# Power_supply.net
KiCad netlist of a schematic drawn in Altium Designer
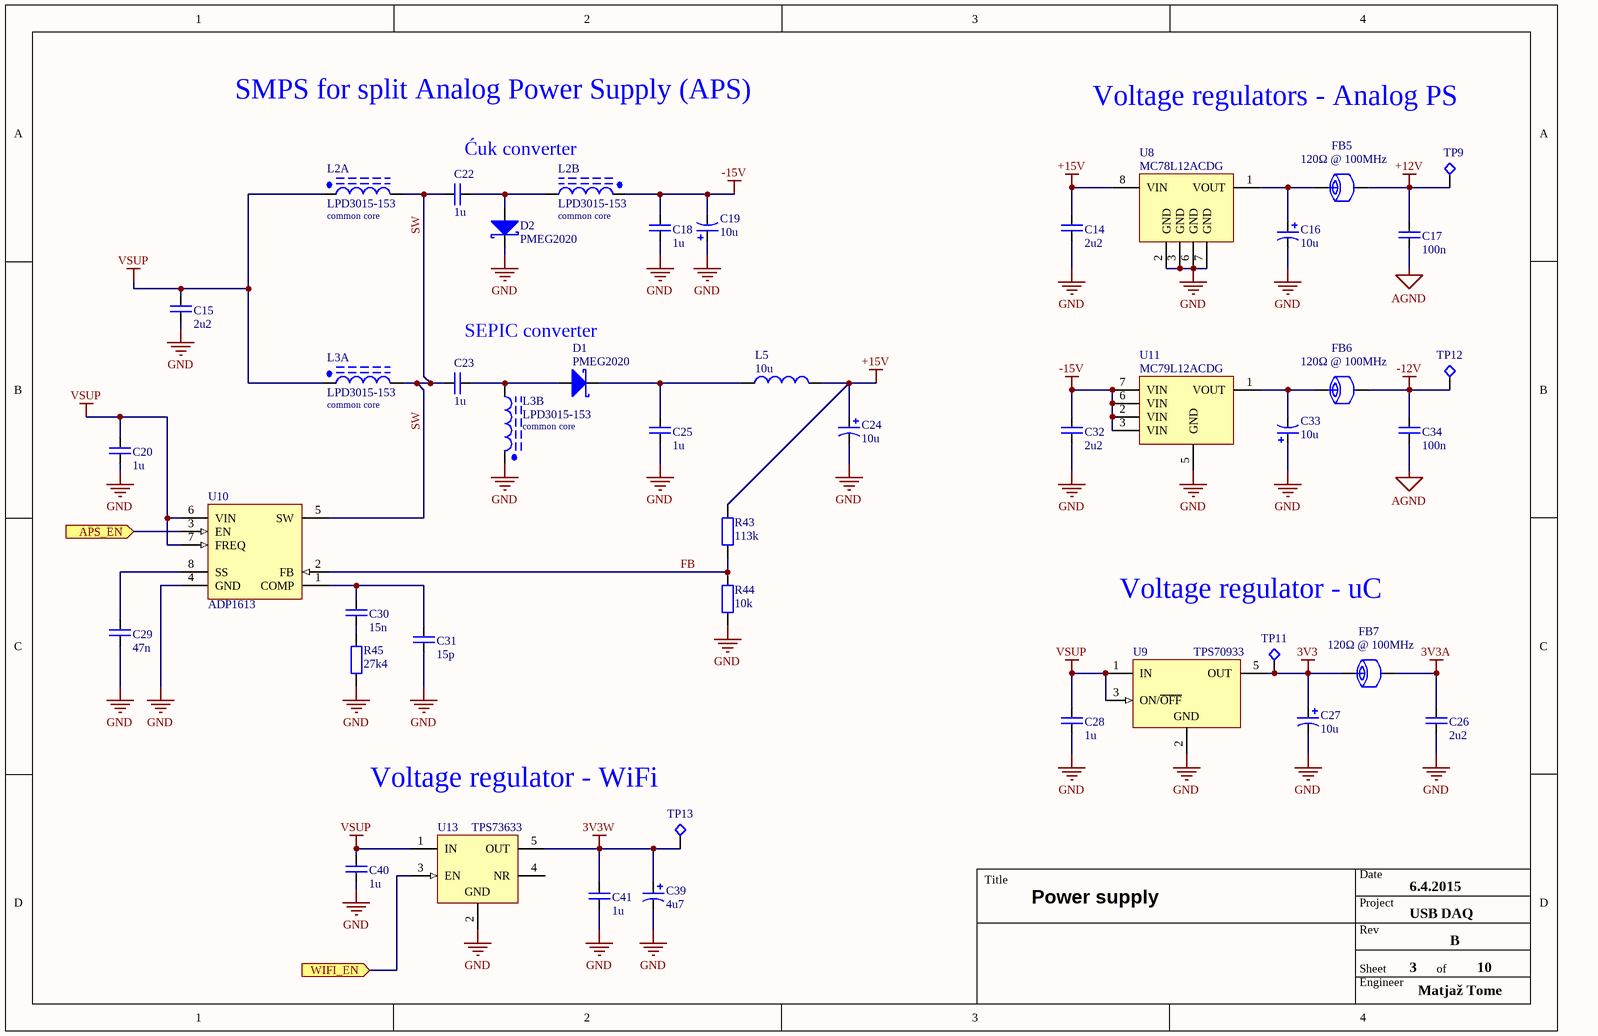
[diagram p0: Power_supply.SchDoc]

(export (version "E")
  (design (tool "Eeschema 10.0.6"))
  (components
    (comp (ref "C14")
      (value "2u2")
      (footprint "C_0603")
      (description "Generic capacitor")
      (libsource (lib "DAQ_REV_B") (part "Capacitor"))
    )
    (comp (ref "C15")
      (value "2u2")
      (footprint "C_0603")
      (description "Generic capacitor")
      (libsource (lib "DAQ_REV_B") (part "Capacitor"))
    )
    (comp (ref "C16")
      (value "10u")
      (footprint "Tantalum Case A")
      (description "Generic polarized capacitor")
      (libsource (lib "DAQ_REV_B") (part "Capacitor - polarized"))
    )
    (comp (ref "C17")
      (value "100n")
      (footprint "C_0603")
      (description "Generic capacitor")
      (libsource (lib "DAQ_REV_B") (part "Capacitor"))
    )
    (comp (ref "C18")
      (value "1u")
      (footprint "C_0603")
      (description "Generic capacitor")
      (libsource (lib "DAQ_REV_B") (part "Capacitor"))
    )
    (comp (ref "C19")
      (value "10u")
      (footprint "Tantalum Case A")
      (description "Generic polarized capacitor")
      (libsource (lib "DAQ_REV_B") (part "Capacitor - polarized"))
    )
    (comp (ref "C20")
      (value "1u")
      (footprint "C_0603")
      (description "Generic capacitor")
      (libsource (lib "DAQ_REV_B") (part "Capacitor"))
    )
    (comp (ref "C22")
      (value "1u")
      (footprint "C_0603")
      (description "Generic capacitor")
      (libsource (lib "DAQ_REV_B") (part "Capacitor"))
    )
    (comp (ref "C23")
      (value "1u")
      (footprint "C_0603")
      (description "Generic capacitor")
      (libsource (lib "DAQ_REV_B") (part "Capacitor"))
    )
    (comp (ref "C24")
      (value "10u")
      (footprint "Tantalum Case A")
      (description "Generic polarized capacitor")
      (libsource (lib "DAQ_REV_B") (part "Capacitor - polarized"))
    )
    (comp (ref "C25")
      (value "1u")
      (footprint "C_0603")
      (description "Generic capacitor")
      (libsource (lib "DAQ_REV_B") (part "Capacitor"))
    )
    (comp (ref "C26")
      (value "2u2")
      (footprint "C_0603")
      (description "Generic capacitor")
      (libsource (lib "DAQ_REV_B") (part "Capacitor"))
    )
    (comp (ref "C27")
      (value "10u")
      (footprint "Tantalum Case A")
      (description "Generic polarized capacitor")
      (libsource (lib "DAQ_REV_B") (part "Capacitor - polarized"))
    )
    (comp (ref "C28")
      (value "1u")
      (footprint "C_0603")
      (description "Generic capacitor")
      (libsource (lib "DAQ_REV_B") (part "Capacitor"))
    )
    (comp (ref "C29")
      (value "47n")
      (footprint "C_0603")
      (description "Generic capacitor")
      (libsource (lib "DAQ_REV_B") (part "Capacitor"))
    )
    (comp (ref "C30")
      (value "15n")
      (footprint "C_0603")
      (description "Generic capacitor")
      (libsource (lib "DAQ_REV_B") (part "Capacitor"))
    )
    (comp (ref "C31")
      (value "15p")
      (footprint "C_0603")
      (description "Generic capacitor")
      (libsource (lib "DAQ_REV_B") (part "Capacitor"))
    )
    (comp (ref "C32")
      (value "2u2")
      (footprint "C_0603")
      (description "Generic capacitor")
      (libsource (lib "DAQ_REV_B") (part "Capacitor"))
    )
    (comp (ref "C33")
      (value "10u")
      (footprint "Tantalum Case A")
      (description "Generic polarized capacitor")
      (libsource (lib "DAQ_REV_B") (part "Capacitor - polarized"))
    )
    (comp (ref "C34")
      (value "100n")
      (footprint "C_0603")
      (description "Generic capacitor")
      (libsource (lib "DAQ_REV_B") (part "Capacitor"))
    )
    (comp (ref "C39")
      (value "4u7")
      (footprint "Tantalum Case A")
      (description "Generic polarized capacitor")
      (libsource (lib "DAQ_REV_B") (part "Capacitor - polarized"))
    )
    (comp (ref "C40")
      (value "1u")
      (footprint "C_0603")
      (description "Generic capacitor")
      (libsource (lib "DAQ_REV_B") (part "Capacitor"))
    )
    (comp (ref "C41")
      (value "1u")
      (footprint "C_0603")
      (description "Generic capacitor")
      (libsource (lib "DAQ_REV_B") (part "Capacitor"))
    )
    (comp (ref "D1")
      (value "PMEG2020")
      (footprint "SOD323")
      (description "Schottky diode, 2A 20V")
      (fields (field (name "PART NUMBER") "XDS0004") (field (name "MANUFACTURER") "Infineon"))
      (libsource (lib "DAQ_REV_B") (part "PMEG2020"))
    )
    (comp (ref "D2")
      (value "PMEG2020")
      (footprint "SOD323")
      (description "Schottky diode, 2A 20V")
      (fields (field (name "PART NUMBER") "XDS0004") (field (name "MANUFACTURER") "Infineon"))
      (libsource (lib "DAQ_REV_B") (part "PMEG2020"))
    )
    (comp (ref "FB5")
      (value "120Ω @ 100MHz")
      (footprint "SMD_0805")
      (description "Ferrite Bead, 0805 [2012 Metric], 120 ohm, 800 mA, BLM21A Series, 0.15 ohm, ± 25%")
      (fields (field (name "MANUFACTURER") "Murata"))
      (libsource (lib "DAQ_REV_B") (part "BLM21AG121SN1D"))
    )
    (comp (ref "FB6")
      (value "120Ω @ 100MHz")
      (footprint "SMD_0805")
      (description "Ferrite Bead, 0805 [2012 Metric], 120 ohm, 800 mA, BLM21A Series, 0.15 ohm, ± 25%")
      (fields (field (name "MANUFACTURER") "Murata"))
      (libsource (lib "DAQ_REV_B") (part "BLM21AG121SN1D"))
    )
    (comp (ref "FB7")
      (value "120Ω @ 100MHz")
      (footprint "SMD_0805")
      (description "Ferrite Bead, 0805 [2012 Metric], 120 ohm, 800 mA, BLM21A Series, 0.15 ohm, ± 25%")
      (fields (field (name "MANUFACTURER") "Murata"))
      (libsource (lib "DAQ_REV_B") (part "BLM21AG121SN1D"))
    )
    (comp (ref "L2")
      (value "LPD3015-153")
      (footprint "LPD3015")
      (description "Inductor, Coupled, 15 µH, 20%, 1.42 ohm, 460 mA, 3mm x 3mm x 1.4mm")
      (fields
        (field (name "MANUFACTURER") "Coilcraft")
        (field (name "TOLERANCE") "20%")
        (field (name "NOTE") "common core")
      )
      (libsource (lib "") (part "LPD3015-153_1"))
    )
    (comp (ref "L3")
      (value "LPD3015-153")
      (footprint "LPD3015")
      (description "Inductor, Coupled, 15 µH, 20%, 1.42 ohm, 460 mA, 3mm x 3mm x 1.4mm")
      (fields
        (field (name "MANUFACTURER") "Coilcraft")
        (field (name "TOLERANCE") "20%")
        (field (name "NOTE") "common core")
      )
      (libsource (lib "") (part "LPD3015-153_1"))
    )
    (comp (ref "L5")
      (value "10u")
      (footprint "IND_SMD_4X4mm")
      (description "Power Inductor (SMD), 10 µH, 770 mA, Shielded, 800 mA, TYS Series, 4mm x 4mm x 1.2mm")
      (fields (field (name "MANUFACTURER") "Laird Technologies") (field (name "TOLERANCE") "20%"))
      (libsource (lib "DAQ_REV_B") (part "TYS4012100M-10"))
    )
    (comp (ref "R43")
      (value "113k")
      (footprint "R_0603")
      (description "Generic resistor")
      (libsource (lib "DAQ_REV_B") (part "Resistor"))
    )
    (comp (ref "R44")
      (value "10k")
      (footprint "R_0603")
      (description "Generic resistor")
      (libsource (lib "DAQ_REV_B") (part "Resistor"))
    )
    (comp (ref "R45")
      (value "27k4")
      (footprint "R_0603")
      (description "Generic resistor")
      (libsource (lib "DAQ_REV_B") (part "Resistor"))
    )
    (comp (ref "TP9")
      (value "testpoint")
      (footprint "TP1_FULL")
      (description "testpoint 1.5mm diameter no hole")
      (fields (field (name "PART NUMBER") "XXC0006"))
      (libsource (lib "DAQ_REV_B") (part "Test Point"))
    )
    (comp (ref "TP11")
      (value "testpoint")
      (footprint "TP1_FULL")
      (description "testpoint 1.5mm diameter no hole")
      (fields (field (name "PART NUMBER") "XXC0006"))
      (libsource (lib "DAQ_REV_B") (part "Test Point"))
    )
    (comp (ref "TP12")
      (value "testpoint")
      (footprint "TP1_FULL")
      (description "testpoint 1.5mm diameter no hole")
      (fields (field (name "PART NUMBER") "XXC0006"))
      (libsource (lib "DAQ_REV_B") (part "Test Point"))
    )
    (comp (ref "TP13")
      (value "testpoint")
      (footprint "TP1_FULL")
      (description "testpoint 1.5mm diameter no hole")
      (fields (field (name "PART NUMBER") "XXC0006"))
      (libsource (lib "DAQ_REV_B") (part "Test Point"))
    )
    (comp (ref "U8")
      (value "MC78L12ACDG")
      (footprint "SOIC8")
      (description "100 mA Positive Voltage Regulator")
      (fields (field (name "PART NUMBER") "XLR0006") (field (name "MANUFACTURER") "ON Semiconductors"))
      (libsource (lib "DAQ_REV_B") (part "78LXX"))
    )
    (comp (ref "U9")
      (value "TPS70933")
      (footprint "SOT23-5")
      (description "1-µA IQ Voltage Regulators with Enable")
      (fields (field (name "PART NUMBER") "XLR0012") (field (name "MANUFACTURER") "Texas Instruments"))
      (libsource (lib "DAQ_REV_B") (part "TPS709XX"))
    )
    (comp (ref "U10")
      (value "ADP1613")
      (footprint "MSOP8")
      (fields (field (name "PART NUMBER") "XSW0008") (field (name "MANUFACTURER") "Analog devices"))
      (libsource (lib "DAQ_REV_B") (part "ADP161X"))
    )
    (comp (ref "U11")
      (value "MC79L12ACDG")
      (footprint "SOIC8")
      (description "100 mA Negative Voltage Regulator")
      (fields (field (name "PART NUMBER") "XLR0007") (field (name "MANUFACTURER") "ON Semiconductors"))
      (libsource (lib "DAQ_REV_B") (part "79LXX"))
    )
    (comp (ref "U13")
      (value "TPS73633")
      (footprint "SOT23-5")
      (description "Cap-Free, NMOS, 400-mA Low-Dropout Regulator with Reverse Current Protection")
      (fields (field (name "PART NUMBER") "XLR0013") (field (name "MANUFACTURER") "Texas instruments"))
      (libsource (lib "DAQ_REV_B") (part "TPS736XX"))
    )
  )
  (nets
    (net (code "1") (name "+12V") (class "Default")
      (node (ref "C17") (pin "2") (pinfunction "2_2") (pintype "passive"))
      (node (ref "FB5") (pin "2") (pintype "passive"))
      (node (ref "TP9") (pin "1") (pinfunction "1_1") (pintype "passive"))
    )
    (net (code "2") (name "+15V") (class "Default")
      (node (ref "C14") (pin "1") (pinfunction "1_1") (pintype "passive"))
      (node (ref "C24") (pin "1") (pinfunction "1_1") (pintype "passive"))
      (node (ref "L5") (pin "2") (pinfunction "2_2") (pintype "passive"))
      (node (ref "R43") (pin "1") (pintype "passive"))
      (node (ref "U8") (pin "8") (pinfunction "VIN_8") (pintype "power_in"))
    )
    (net (code "3") (name "-12V") (class "Default")
      (node (ref "C34") (pin "2") (pinfunction "2_2") (pintype "passive"))
      (node (ref "FB6") (pin "2") (pintype "passive"))
      (node (ref "TP12") (pin "1") (pinfunction "1_1") (pintype "passive"))
    )
    (net (code "4") (name "-15V") (class "Default")
      (node (ref "C18") (pin "1") (pinfunction "1_1") (pintype "passive"))
      (node (ref "C19") (pin "2") (pinfunction "2_2") (pintype "passive"))
      (node (ref "C32") (pin "1") (pinfunction "1_1") (pintype "passive"))
      (node (ref "L2") (pin "4") (pinfunction "4_4") (pintype "passive"))
      (node (ref "U11") (pin "2") (pinfunction "VIN_2") (pintype "power_in"))
      (node (ref "U11") (pin "3") (pinfunction "VIN_3") (pintype "power_in"))
      (node (ref "U11") (pin "6") (pinfunction "VIN_6") (pintype "power_in"))
      (node (ref "U11") (pin "7") (pinfunction "VIN_7") (pintype "power_in"))
    )
    (net (code "5") (name "/APS_EN") (class "Default")
      (node (ref "U10") (pin "3") (pinfunction "EN_3") (pintype "input"))
    )
    (net (code "6") (name "/FB") (class "Default")
      (node (ref "R43") (pin "2") (pintype "passive"))
      (node (ref "R44") (pin "2") (pintype "passive"))
      (node (ref "U10") (pin "2") (pinfunction "FB_2") (pintype "input"))
    )
    (net (code "7") (name "/SW") (class "Default")
      (node (ref "C22") (pin "1") (pinfunction "1_1") (pintype "passive"))
      (node (ref "C23") (pin "1") (pinfunction "1_1") (pintype "passive"))
      (node (ref "L2") (pin "2") (pinfunction "2_2") (pintype "passive"))
      (node (ref "L3") (pin "2") (pinfunction "2_2") (pintype "passive"))
      (node (ref "U10") (pin "5") (pinfunction "SW_5") (pintype "passive"))
    )
    (net (code "8") (name "/WIFI_EN") (class "Default")
      (node (ref "U13") (pin "3") (pinfunction "EN_3") (pintype "input"))
    )
    (net (code "9") (name "3V3") (class "Default")
      (node (ref "C27") (pin "1") (pinfunction "1_1") (pintype "passive"))
      (node (ref "FB7") (pin "1") (pintype "passive"))
      (node (ref "TP11") (pin "1") (pinfunction "1_1") (pintype "passive"))
      (node (ref "U9") (pin "5") (pinfunction "OUT_5") (pintype "power_in"))
    )
    (net (code "10") (name "3V3A") (class "Default")
      (node (ref "C26") (pin "1") (pinfunction "1_1") (pintype "passive"))
      (node (ref "FB7") (pin "2") (pintype "passive"))
    )
    (net (code "11") (name "3V3W") (class "Default")
      (node (ref "C39") (pin "1") (pinfunction "1_1") (pintype "passive"))
      (node (ref "C41") (pin "1") (pinfunction "1_1") (pintype "passive"))
      (node (ref "TP13") (pin "1") (pinfunction "1_1") (pintype "passive"))
      (node (ref "U13") (pin "5") (pinfunction "OUT_5") (pintype "power_in"))
    )
    (net (code "12") (name "AGND") (class "Default")
      (node (ref "C17") (pin "1") (pinfunction "1_1") (pintype "passive"))
      (node (ref "C34") (pin "1") (pinfunction "1_1") (pintype "passive"))
    )
    (net (code "13") (name "GND") (class "Default")
      (node (ref "C14") (pin "2") (pinfunction "2_2") (pintype "passive"))
      (node (ref "C15") (pin "1") (pinfunction "1_1") (pintype "passive"))
      (node (ref "C16") (pin "2") (pinfunction "2_2") (pintype "passive"))
      (node (ref "C18") (pin "2") (pinfunction "2_2") (pintype "passive"))
      (node (ref "C19") (pin "1") (pinfunction "1_1") (pintype "passive"))
      (node (ref "C20") (pin "2") (pinfunction "2_2") (pintype "passive"))
      (node (ref "C24") (pin "2") (pinfunction "2_2") (pintype "passive"))
      (node (ref "C25") (pin "2") (pinfunction "2_2") (pintype "passive"))
      (node (ref "C26") (pin "2") (pinfunction "2_2") (pintype "passive"))
      (node (ref "C27") (pin "2") (pinfunction "2_2") (pintype "passive"))
      (node (ref "C28") (pin "2") (pinfunction "2_2") (pintype "passive"))
      (node (ref "C29") (pin "2") (pinfunction "2_2") (pintype "passive"))
      (node (ref "C31") (pin "2") (pinfunction "2_2") (pintype "passive"))
      (node (ref "C32") (pin "2") (pinfunction "2_2") (pintype "passive"))
      (node (ref "C33") (pin "1") (pinfunction "1_1") (pintype "passive"))
      (node (ref "C39") (pin "2") (pinfunction "2_2") (pintype "passive"))
      (node (ref "C40") (pin "2") (pinfunction "2_2") (pintype "passive"))
      (node (ref "C41") (pin "2") (pinfunction "2_2") (pintype "passive"))
      (node (ref "D2") (pin "2") (pinfunction "K_2") (pintype "passive"))
      (node (ref "L3") (pin "4") (pinfunction "4_4") (pintype "passive"))
      (node (ref "R44") (pin "1") (pintype "passive"))
      (node (ref "R45") (pin "1") (pintype "passive"))
      (node (ref "U10") (pin "4") (pinfunction "GND_4") (pintype "power_in"))
      (node (ref "U11") (pin "5") (pinfunction "GND_5") (pintype "power_in"))
      (node (ref "U13") (pin "2") (pinfunction "GND_2") (pintype "power_in"))
      (node (ref "U8") (pin "2") (pinfunction "GND_2") (pintype "power_in"))
      (node (ref "U8") (pin "3") (pinfunction "GND_3") (pintype "power_in"))
      (node (ref "U8") (pin "6") (pinfunction "GND_6") (pintype "power_in"))
      (node (ref "U8") (pin "7") (pinfunction "GND_7") (pintype "power_in"))
      (node (ref "U9") (pin "2") (pinfunction "GND_2") (pintype "power_in"))
    )
    (net (code "14") (name "Net-(C30-Pad2)") (class "Default")
      (node (ref "C30") (pin "2") (pinfunction "2_2") (pintype "passive"))
      (node (ref "R45") (pin "2") (pintype "passive"))
    )
    (net (code "15") (name "Net-(D1-A)") (class "Default")
      (node (ref "C23") (pin "2") (pinfunction "2_2") (pintype "passive"))
      (node (ref "D1") (pin "1") (pinfunction "A_1") (pintype "passive"))
      (node (ref "L3") (pin "3") (pinfunction "3_3") (pintype "passive"))
    )
    (net (code "16") (name "Net-(D1-K)") (class "Default")
      (node (ref "C25") (pin "1") (pinfunction "1_1") (pintype "passive"))
      (node (ref "D1") (pin "2") (pinfunction "K_2") (pintype "passive"))
      (node (ref "L5") (pin "1") (pinfunction "1_1") (pintype "passive"))
    )
    (net (code "17") (name "Net-(D2-A)") (class "Default")
      (node (ref "C22") (pin "2") (pinfunction "2_2") (pintype "passive"))
      (node (ref "D2") (pin "1") (pinfunction "A_1") (pintype "passive"))
      (node (ref "L2") (pin "3") (pinfunction "3_3") (pintype "passive"))
    )
    (net (code "18") (name "Net-(U8-VOUT)") (class "Default")
      (node (ref "C16") (pin "1") (pinfunction "1_1") (pintype "passive"))
      (node (ref "FB5") (pin "1") (pintype "passive"))
      (node (ref "U8") (pin "1") (pinfunction "VOUT_1") (pintype "power_in"))
    )
    (net (code "19") (name "Net-(U10-COMP)") (class "Default")
      (node (ref "C30") (pin "1") (pinfunction "1_1") (pintype "passive"))
      (node (ref "C31") (pin "1") (pinfunction "1_1") (pintype "passive"))
      (node (ref "U10") (pin "1") (pinfunction "COMP_1") (pintype "passive"))
    )
    (net (code "20") (name "Net-(U10-SS)") (class "Default")
      (node (ref "C29") (pin "1") (pinfunction "1_1") (pintype "passive"))
      (node (ref "U10") (pin "8") (pinfunction "SS_8") (pintype "passive"))
    )
    (net (code "21") (name "Net-(U11-VOUT)") (class "Default")
      (node (ref "C33") (pin "2") (pinfunction "2_2") (pintype "passive"))
      (node (ref "FB6") (pin "1") (pintype "passive"))
      (node (ref "U11") (pin "1") (pinfunction "VOUT_1") (pintype "power_in"))
    )
    (net (code "22") (name "VSUP") (class "Default")
      (node (ref "C15") (pin "2") (pinfunction "2_2") (pintype "passive"))
      (node (ref "C20") (pin "1") (pinfunction "1_1") (pintype "passive"))
      (node (ref "C28") (pin "1") (pinfunction "1_1") (pintype "passive"))
      (node (ref "C40") (pin "1") (pinfunction "1_1") (pintype "passive"))
      (node (ref "L2") (pin "1") (pinfunction "1_1") (pintype "passive"))
      (node (ref "L3") (pin "1") (pinfunction "1_1") (pintype "passive"))
      (node (ref "U10") (pin "6") (pinfunction "VIN_6") (pintype "power_in"))
      (node (ref "U10") (pin "7") (pinfunction "FREQ_7") (pintype "input"))
      (node (ref "U13") (pin "1") (pinfunction "IN_1") (pintype "power_in"))
      (node (ref "U9") (pin "1") (pinfunction "IN_1") (pintype "power_in"))
      (node (ref "U9") (pin "3") (pinfunction "ON/~{OFF}_3") (pintype "input"))
    )
    (net (code "23") (name "unconnected-(U13-NR-Pad4)") (class "Default")
      (node (ref "U13") (pin "4") (pinfunction "NR_4") (pintype "passive"))
    )
  )
)
